# T07_-BOARD_V8.net
KiCad netlist of a schematic drawn in EAGLE
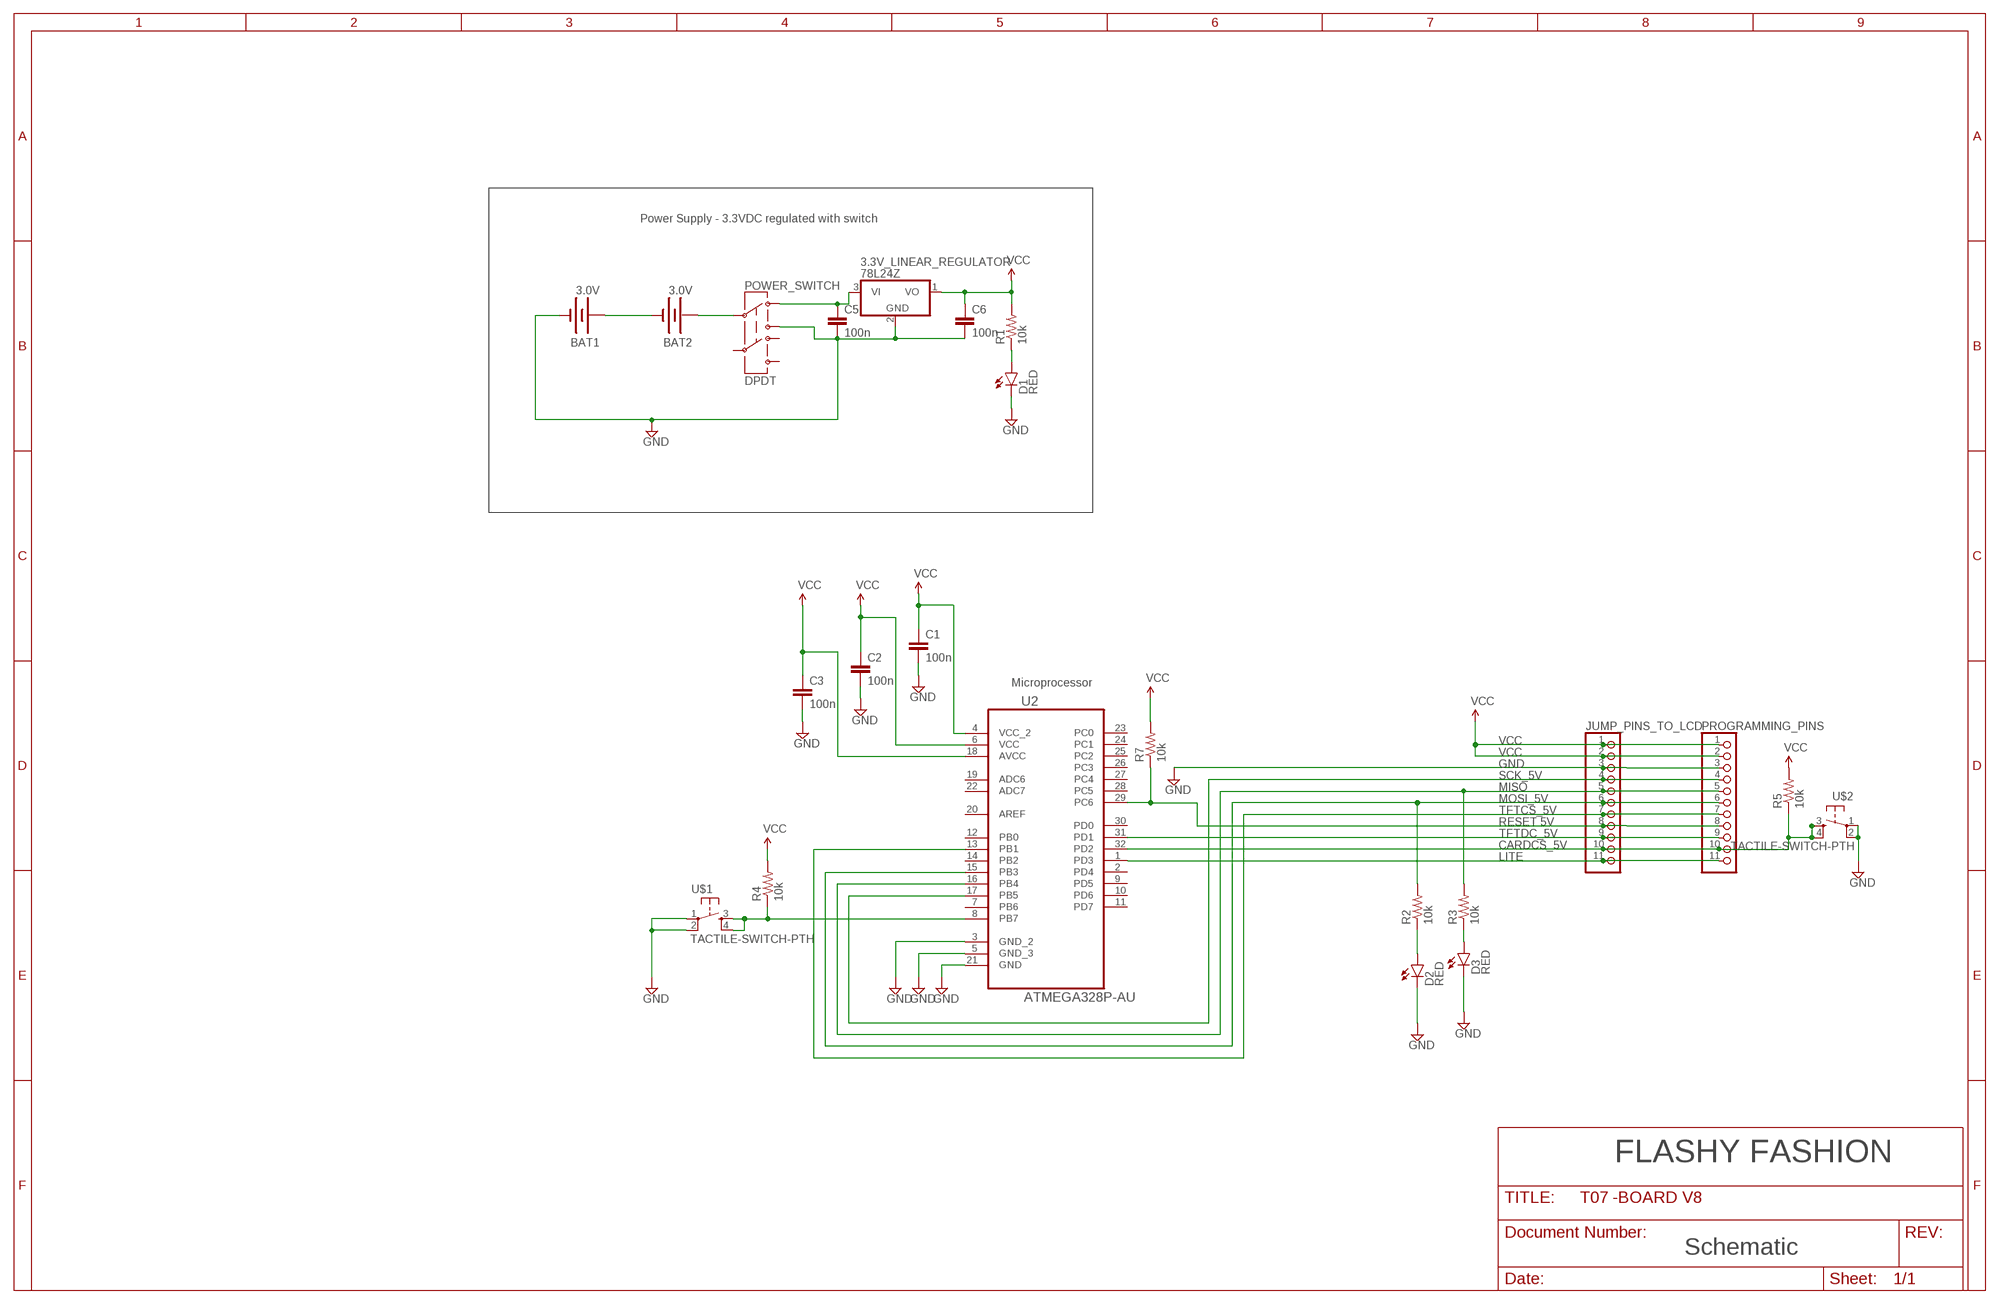
[diagram p0: schematic, sheet 1]

(export (version "E")
  (design (tool "Eeschema 10.0.6"))
  (components
    (comp (ref "3.3V_LINEAR_REGULATOR")
      (value "78L24Z")
      (footprint "eagle-import:TO92")
      (libsource (lib "eagle-import") (part "78ZL24"))
    )
    (comp (ref "BAT1")
      (value "3.0V")
      (footprint "eagle-import:BATTCON_245MM_PTH")
      (libsource (lib "eagle-import") (part "BATTERY245PTH"))
    )
    (comp (ref "BAT2")
      (value "3.0V")
      (footprint "eagle-import:BATTCON_245MM_PTH")
      (libsource (lib "eagle-import") (part "BATTERY245PTH"))
    )
    (comp (ref "C1")
      (value "100n")
      (footprint "eagle-import:1206")
      (libsource (lib "eagle-import") (part "CAP1206"))
    )
    (comp (ref "C2")
      (value "100n")
      (footprint "eagle-import:1206")
      (libsource (lib "eagle-import") (part "CAP1206"))
    )
    (comp (ref "C3")
      (value "100n")
      (footprint "eagle-import:1206")
      (libsource (lib "eagle-import") (part "CAP1206"))
    )
    (comp (ref "C5")
      (value "100n")
      (footprint "eagle-import:1206")
      (libsource (lib "eagle-import") (part "CAP1206"))
    )
    (comp (ref "C6")
      (value "100n")
      (footprint "eagle-import:1206")
      (libsource (lib "eagle-import") (part "SparkFun-Passives_CAP1206"))
    )
    (comp (ref "D1")
      (value "RED")
      (footprint "eagle-import:LED-1206")
      (libsource (lib "eagle-import") (part "LED-BLUE1206"))
    )
    (comp (ref "D2")
      (value "RED")
      (footprint "eagle-import:LED-1206")
      (libsource (lib "eagle-import") (part "LED-BLUE1206"))
    )
    (comp (ref "D3")
      (value "RED")
      (footprint "eagle-import:LED-1206")
      (libsource (lib "eagle-import") (part "LED-BLUE1206"))
    )
    (comp (ref "JUMP_PINS_TO_LCD")
      (value "HEADER-1X1176MIL")
      (footprint "eagle-import:1X11_ROUND_76")
      (libsource (lib "eagle-import") (part "HEADER-1X1176MIL"))
    )
    (comp (ref "POWER_SWITCH")
      (value "DPDT")
      (footprint "eagle-import:AYZ0202")
      (libsource (lib "eagle-import") (part "SWITCH-DPDTAYZ0202"))
    )
    (comp (ref "PROGRAMMING_PINS")
      (value "HEADER-1X1176MIL")
      (footprint "eagle-import:1X11_ROUND_76")
      (libsource (lib "eagle-import") (part "HEADER-1X1176MIL"))
    )
    (comp (ref "R1")
      (value "10k")
      (footprint "eagle-import:1206")
      (libsource (lib "eagle-import") (part "SparkFun-Resistors_RESISTOR1206"))
    )
    (comp (ref "R2")
      (value "10k")
      (footprint "eagle-import:1206")
      (libsource (lib "eagle-import") (part "SparkFun-Resistors_RESISTOR1206"))
    )
    (comp (ref "R3")
      (value "10k")
      (footprint "eagle-import:1206")
      (libsource (lib "eagle-import") (part "SparkFun-Resistors_RESISTOR1206"))
    )
    (comp (ref "R4")
      (value "10k")
      (footprint "eagle-import:1206")
      (libsource (lib "eagle-import") (part "RESISTOR1206"))
    )
    (comp (ref "R5")
      (value "10k")
      (footprint "eagle-import:1206")
      (libsource (lib "eagle-import") (part "RESISTOR1206"))
    )
    (comp (ref "R7")
      (value "10k")
      (footprint "eagle-import:1206")
      (libsource (lib "eagle-import") (part "RESISTOR1206"))
    )
    (comp (ref "U$1")
      (value "TACTILE-SWITCH-PTH")
      (footprint "eagle-import:TAC-SWITCH-PTH")
      (libsource (lib "eagle-import") (part "TACTILE-SWITCH-PTH"))
    )
    (comp (ref "U$2")
      (value "TACTILE-SWITCH-PTH")
      (footprint "eagle-import:TAC-SWITCH-PTH")
      (libsource (lib "eagle-import") (part "TACTILE-SWITCH-PTH"))
    )
    (comp (ref "U2")
      (value "ATMEGA328P-AU")
      (footprint "eagle-import:QFP80P900X900X120-32N")
      (libsource (lib "eagle-import") (part "ATMEGA328P-AU"))
    )
  )
  (nets
    (net (code "1") (name "/CARDCS_5V") (class "Default")
      (node (ref "JUMP_PINS_TO_LCD") (pin "10") (pinfunction "10_10") (pintype "passive"))
      (node (ref "PROGRAMMING_PINS") (pin "10") (pinfunction "10_10") (pintype "passive"))
      (node (ref "R5") (pin "1") (pinfunction "1_1") (pintype "passive"))
      (node (ref "U$2") (pin "3") (pinfunction "3_3") (pintype "passive"))
      (node (ref "U$2") (pin "4") (pinfunction "4_4") (pintype "passive"))
      (node (ref "U2") (pin "32") (pinfunction "PD2_32") (pintype "bidirectional"))
    )
    (net (code "2") (name "/LITE") (class "Default")
      (node (ref "JUMP_PINS_TO_LCD") (pin "11") (pinfunction "11_11") (pintype "passive"))
      (node (ref "PROGRAMMING_PINS") (pin "11") (pinfunction "11_11") (pintype "passive"))
      (node (ref "U2") (pin "1") (pinfunction "PD3_1") (pintype "bidirectional"))
    )
    (net (code "3") (name "/MISO") (class "Default")
      (node (ref "JUMP_PINS_TO_LCD") (pin "5") (pinfunction "5_5") (pintype "passive"))
      (node (ref "PROGRAMMING_PINS") (pin "5") (pinfunction "5_5") (pintype "passive"))
      (node (ref "R3") (pin "2") (pinfunction "2_2") (pintype "passive"))
      (node (ref "U2") (pin "16") (pinfunction "PB4_16") (pintype "bidirectional"))
    )
    (net (code "4") (name "/MOSI_5V") (class "Default")
      (node (ref "JUMP_PINS_TO_LCD") (pin "6") (pinfunction "6_6") (pintype "passive"))
      (node (ref "PROGRAMMING_PINS") (pin "6") (pinfunction "6_6") (pintype "passive"))
      (node (ref "R2") (pin "2") (pinfunction "2_2") (pintype "passive"))
      (node (ref "U2") (pin "15") (pinfunction "PB3_15") (pintype "bidirectional"))
    )
    (net (code "5") (name "/SCK_5V") (class "Default")
      (node (ref "JUMP_PINS_TO_LCD") (pin "4") (pinfunction "4_4") (pintype "passive"))
      (node (ref "PROGRAMMING_PINS") (pin "4") (pinfunction "4_4") (pintype "passive"))
      (node (ref "U2") (pin "17") (pinfunction "PB5_17") (pintype "bidirectional"))
    )
    (net (code "6") (name "/TFTCS_5V") (class "Default")
      (node (ref "JUMP_PINS_TO_LCD") (pin "7") (pinfunction "7_7") (pintype "passive"))
      (node (ref "PROGRAMMING_PINS") (pin "7") (pinfunction "7_7") (pintype "passive"))
      (node (ref "U2") (pin "13") (pinfunction "PB1_13") (pintype "bidirectional"))
    )
    (net (code "7") (name "/TFTDC_5V") (class "Default")
      (node (ref "JUMP_PINS_TO_LCD") (pin "9") (pinfunction "9_9") (pintype "passive"))
      (node (ref "PROGRAMMING_PINS") (pin "9") (pinfunction "9_9") (pintype "passive"))
      (node (ref "U2") (pin "31") (pinfunction "PD1_31") (pintype "bidirectional"))
    )
    (net (code "8") (name "GND") (class "Default")
      (node (ref "3.3V_LINEAR_REGULATOR") (pin "2") (pinfunction "GND_2") (pintype "passive"))
      (node (ref "BAT1") (pin "2") (pinfunction "-_2") (pintype "power_in"))
      (node (ref "C1") (pin "2") (pinfunction "2_2") (pintype "passive"))
      (node (ref "C2") (pin "2") (pinfunction "2_2") (pintype "passive"))
      (node (ref "C3") (pin "2") (pinfunction "2_2") (pintype "passive"))
      (node (ref "C5") (pin "2") (pinfunction "2_2") (pintype "passive"))
      (node (ref "C6") (pin "2") (pinfunction "2_2") (pintype "passive"))
      (node (ref "D1") (pin "C") (pinfunction "C_C") (pintype "passive"))
      (node (ref "D2") (pin "C") (pinfunction "C_C") (pintype "passive"))
      (node (ref "D3") (pin "C") (pinfunction "C_C") (pintype "passive"))
      (node (ref "JUMP_PINS_TO_LCD") (pin "3") (pinfunction "3_3") (pintype "passive"))
      (node (ref "POWER_SWITCH") (pin "3") (pinfunction "3_3") (pintype "bidirectional"))
      (node (ref "PROGRAMMING_PINS") (pin "3") (pinfunction "3_3") (pintype "passive"))
      (node (ref "U$1") (pin "1") (pinfunction "1_1") (pintype "passive"))
      (node (ref "U$1") (pin "2") (pinfunction "2_2") (pintype "passive"))
      (node (ref "U$2") (pin "1") (pinfunction "1_1") (pintype "passive"))
      (node (ref "U$2") (pin "2") (pinfunction "2_2") (pintype "passive"))
      (node (ref "U2") (pin "21") (pinfunction "GND_21") (pintype "passive"))
      (node (ref "U2") (pin "3") (pinfunction "GND_2_3") (pintype "passive"))
      (node (ref "U2") (pin "5") (pinfunction "GND_3_5") (pintype "passive"))
    )
    (net (code "9") (name "Net-(3.3V_LINEAR_REGULATOR-VI)") (class "Default")
      (node (ref "3.3V_LINEAR_REGULATOR") (pin "3") (pinfunction "VI_3") (pintype "input"))
      (node (ref "C5") (pin "1") (pinfunction "1_1") (pintype "passive"))
      (node (ref "POWER_SWITCH") (pin "1") (pinfunction "1_1") (pintype "bidirectional"))
    )
    (net (code "10") (name "Net-(BAT1-+)") (class "Default")
      (node (ref "BAT1") (pin "3") (pinfunction "+_3") (pintype "power_in"))
      (node (ref "BAT2") (pin "2") (pinfunction "-_2") (pintype "power_in"))
    )
    (net (code "11") (name "Net-(BAT2-+)") (class "Default")
      (node (ref "BAT2") (pin "3") (pinfunction "+_3") (pintype "power_in"))
      (node (ref "POWER_SWITCH") (pin "2") (pinfunction "2_2") (pintype "bidirectional"))
    )
    (net (code "12") (name "Net-(D1-PadA)") (class "Default")
      (node (ref "D1") (pin "A") (pinfunction "A_A") (pintype "passive"))
      (node (ref "R1") (pin "1") (pinfunction "1_1") (pintype "passive"))
    )
    (net (code "13") (name "Net-(D2-PadA)") (class "Default")
      (node (ref "D2") (pin "A") (pinfunction "A_A") (pintype "passive"))
      (node (ref "R2") (pin "1") (pinfunction "1_1") (pintype "passive"))
    )
    (net (code "14") (name "Net-(D3-PadA)") (class "Default")
      (node (ref "D3") (pin "A") (pinfunction "A_A") (pintype "passive"))
      (node (ref "R3") (pin "1") (pinfunction "1_1") (pintype "passive"))
    )
    (net (code "15") (name "Net-(U2-PB7)") (class "Default")
      (node (ref "R4") (pin "1") (pinfunction "1_1") (pintype "passive"))
      (node (ref "U$1") (pin "3") (pinfunction "3_3") (pintype "passive"))
      (node (ref "U$1") (pin "4") (pinfunction "4_4") (pintype "passive"))
      (node (ref "U2") (pin "8") (pinfunction "PB7_8") (pintype "bidirectional"))
    )
    (net (code "16") (name "Net-(U2-PC6)") (class "Default")
      (node (ref "JUMP_PINS_TO_LCD") (pin "8") (pinfunction "8_8") (pintype "passive"))
      (node (ref "PROGRAMMING_PINS") (pin "8") (pinfunction "8_8") (pintype "passive"))
      (node (ref "R7") (pin "1") (pinfunction "1_1") (pintype "passive"))
      (node (ref "U2") (pin "29") (pinfunction "PC6_29") (pintype "bidirectional"))
    )
    (net (code "17") (name "VCC") (class "Default")
      (node (ref "3.3V_LINEAR_REGULATOR") (pin "1") (pinfunction "VO_1") (pintype "passive"))
      (node (ref "C1") (pin "1") (pinfunction "1_1") (pintype "passive"))
      (node (ref "C2") (pin "1") (pinfunction "1_1") (pintype "passive"))
      (node (ref "C3") (pin "1") (pinfunction "1_1") (pintype "passive"))
      (node (ref "C6") (pin "1") (pinfunction "1_1") (pintype "passive"))
      (node (ref "JUMP_PINS_TO_LCD") (pin "1") (pinfunction "1_1") (pintype "passive"))
      (node (ref "JUMP_PINS_TO_LCD") (pin "2") (pinfunction "2_2") (pintype "passive"))
      (node (ref "PROGRAMMING_PINS") (pin "1") (pinfunction "1_1") (pintype "passive"))
      (node (ref "PROGRAMMING_PINS") (pin "2") (pinfunction "2_2") (pintype "passive"))
      (node (ref "R1") (pin "2") (pinfunction "2_2") (pintype "passive"))
      (node (ref "R4") (pin "2") (pinfunction "2_2") (pintype "passive"))
      (node (ref "R5") (pin "2") (pinfunction "2_2") (pintype "passive"))
      (node (ref "R7") (pin "2") (pinfunction "2_2") (pintype "passive"))
      (node (ref "U2") (pin "18") (pinfunction "AVCC_18") (pintype "power_in"))
      (node (ref "U2") (pin "4") (pinfunction "VCC_2_4") (pintype "power_in"))
      (node (ref "U2") (pin "6") (pinfunction "VCC_6") (pintype "power_in"))
    )
    (net (code "18") (name "unconnected-(POWER_SWITCH-Pad4)") (class "Default")
      (node (ref "POWER_SWITCH") (pin "4") (pinfunction "4_4") (pintype "bidirectional"))
    )
    (net (code "19") (name "unconnected-(POWER_SWITCH-Pad5)") (class "Default")
      (node (ref "POWER_SWITCH") (pin "5") (pinfunction "5_5") (pintype "bidirectional"))
    )
    (net (code "20") (name "unconnected-(POWER_SWITCH-Pad6)") (class "Default")
      (node (ref "POWER_SWITCH") (pin "6") (pinfunction "6_6") (pintype "bidirectional"))
    )
    (net (code "21") (name "unconnected-(U2-ADC6-Pad19)") (class "Default")
      (node (ref "U2") (pin "19") (pinfunction "ADC6_19") (pintype "input"))
    )
    (net (code "22") (name "unconnected-(U2-ADC7-Pad22)") (class "Default")
      (node (ref "U2") (pin "22") (pinfunction "ADC7_22") (pintype "input"))
    )
    (net (code "23") (name "unconnected-(U2-AREF-Pad20)") (class "Default")
      (node (ref "U2") (pin "20") (pinfunction "AREF_20") (pintype "input"))
    )
    (net (code "24") (name "unconnected-(U2-PB0-Pad12)") (class "Default")
      (node (ref "U2") (pin "12") (pinfunction "PB0_12") (pintype "bidirectional"))
    )
    (net (code "25") (name "unconnected-(U2-PB2-Pad14)") (class "Default")
      (node (ref "U2") (pin "14") (pinfunction "PB2_14") (pintype "bidirectional"))
    )
    (net (code "26") (name "unconnected-(U2-PB6-Pad7)") (class "Default")
      (node (ref "U2") (pin "7") (pinfunction "PB6_7") (pintype "bidirectional"))
    )
    (net (code "27") (name "unconnected-(U2-PC0-Pad23)") (class "Default")
      (node (ref "U2") (pin "23") (pinfunction "PC0_23") (pintype "bidirectional"))
    )
    (net (code "28") (name "unconnected-(U2-PC1-Pad24)") (class "Default")
      (node (ref "U2") (pin "24") (pinfunction "PC1_24") (pintype "bidirectional"))
    )
    (net (code "29") (name "unconnected-(U2-PC2-Pad25)") (class "Default")
      (node (ref "U2") (pin "25") (pinfunction "PC2_25") (pintype "bidirectional"))
    )
    (net (code "30") (name "unconnected-(U2-PC3-Pad26)") (class "Default")
      (node (ref "U2") (pin "26") (pinfunction "PC3_26") (pintype "bidirectional"))
    )
    (net (code "31") (name "unconnected-(U2-PC4-Pad27)") (class "Default")
      (node (ref "U2") (pin "27") (pinfunction "PC4_27") (pintype "bidirectional"))
    )
    (net (code "32") (name "unconnected-(U2-PC5-Pad28)") (class "Default")
      (node (ref "U2") (pin "28") (pinfunction "PC5_28") (pintype "bidirectional"))
    )
    (net (code "33") (name "unconnected-(U2-PD0-Pad30)") (class "Default")
      (node (ref "U2") (pin "30") (pinfunction "PD0_30") (pintype "bidirectional"))
    )
    (net (code "34") (name "unconnected-(U2-PD4-Pad2)") (class "Default")
      (node (ref "U2") (pin "2") (pinfunction "PD4_2") (pintype "bidirectional"))
    )
    (net (code "35") (name "unconnected-(U2-PD5-Pad9)") (class "Default")
      (node (ref "U2") (pin "9") (pinfunction "PD5_9") (pintype "bidirectional"))
    )
    (net (code "36") (name "unconnected-(U2-PD6-Pad10)") (class "Default")
      (node (ref "U2") (pin "10") (pinfunction "PD6_10") (pintype "bidirectional"))
    )
    (net (code "37") (name "unconnected-(U2-PD7-Pad11)") (class "Default")
      (node (ref "U2") (pin "11") (pinfunction "PD7_11") (pintype "bidirectional"))
    )
  )
)
